# design.net
KiCad netlist of a schematic drawn in Altium Designer
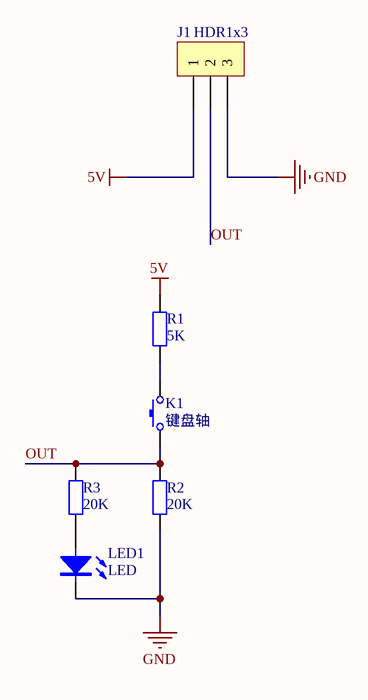
[diagram p0: 装甲板（行程开关方案）.SchDoc]

(export (version "E")
  (design (tool "Eeschema 10.0.6"))
  (components
    (comp (ref "J1")
      (value "HDR1x3")
      (footprint "排针排母 3P 2.54mm")
      (description "Connector")
      (libsource (lib "General") (part "HDR1x3"))
    )
    (comp (ref "K1")
      (value "键盘轴")
      (footprint "键盘轴（单端固定）")
      (description "Key")
      (libsource (lib "General") (part "键盘轴"))
    )
    (comp (ref "LED1") (value "LED") (footprint "LED_0603") (libsource (lib "General") (part "LED")))
    (comp (ref "R1")
      (value "5K")
      (footprint "0603_R")
      (description "Resistor")
      (libsource (lib "General") (part "RES"))
    )
    (comp (ref "R2")
      (value "20K")
      (footprint "0603_R")
      (description "Resistor")
      (libsource (lib "General") (part "RES"))
    )
    (comp (ref "R3")
      (value "20K")
      (footprint "0603_R")
      (description "Resistor")
      (libsource (lib "General") (part "RES"))
    )
  )
  (nets
    (net (code "1") (name "/OUT") (class "Default")
      (node (ref "J1") (pin "2") (pinfunction "2_2") (pintype "passive"))
      (node (ref "K1") (pin "1") (pinfunction "1_1") (pintype "passive"))
      (node (ref "R2") (pin "2") (pinfunction "2_2") (pintype "passive"))
      (node (ref "R3") (pin "2") (pinfunction "2_2") (pintype "passive"))
    )
    (net (code "2") (name "5V") (class "Default")
      (node (ref "J1") (pin "1") (pinfunction "1_1") (pintype "passive"))
      (node (ref "R1") (pin "2") (pinfunction "2_2") (pintype "passive"))
    )
    (net (code "3") (name "GND") (class "Default")
      (node (ref "J1") (pin "3") (pinfunction "3_3") (pintype "passive"))
      (node (ref "LED1") (pin "2") (pinfunction "C_2") (pintype "passive"))
      (node (ref "R2") (pin "1") (pinfunction "1_1") (pintype "passive"))
    )
    (net (code "4") (name "Net-(K1-Pad2)") (class "Default")
      (node (ref "K1") (pin "2") (pinfunction "2_2") (pintype "passive"))
      (node (ref "R1") (pin "1") (pinfunction "1_1") (pintype "passive"))
    )
    (net (code "5") (name "Net-(LED1-A)") (class "Default")
      (node (ref "LED1") (pin "1") (pinfunction "A_1") (pintype "passive"))
      (node (ref "R3") (pin "1") (pinfunction "1_1") (pintype "passive"))
    )
  )
)
